# M3_Chip.net
KiCad netlist of a schematic drawn in Altium Designer
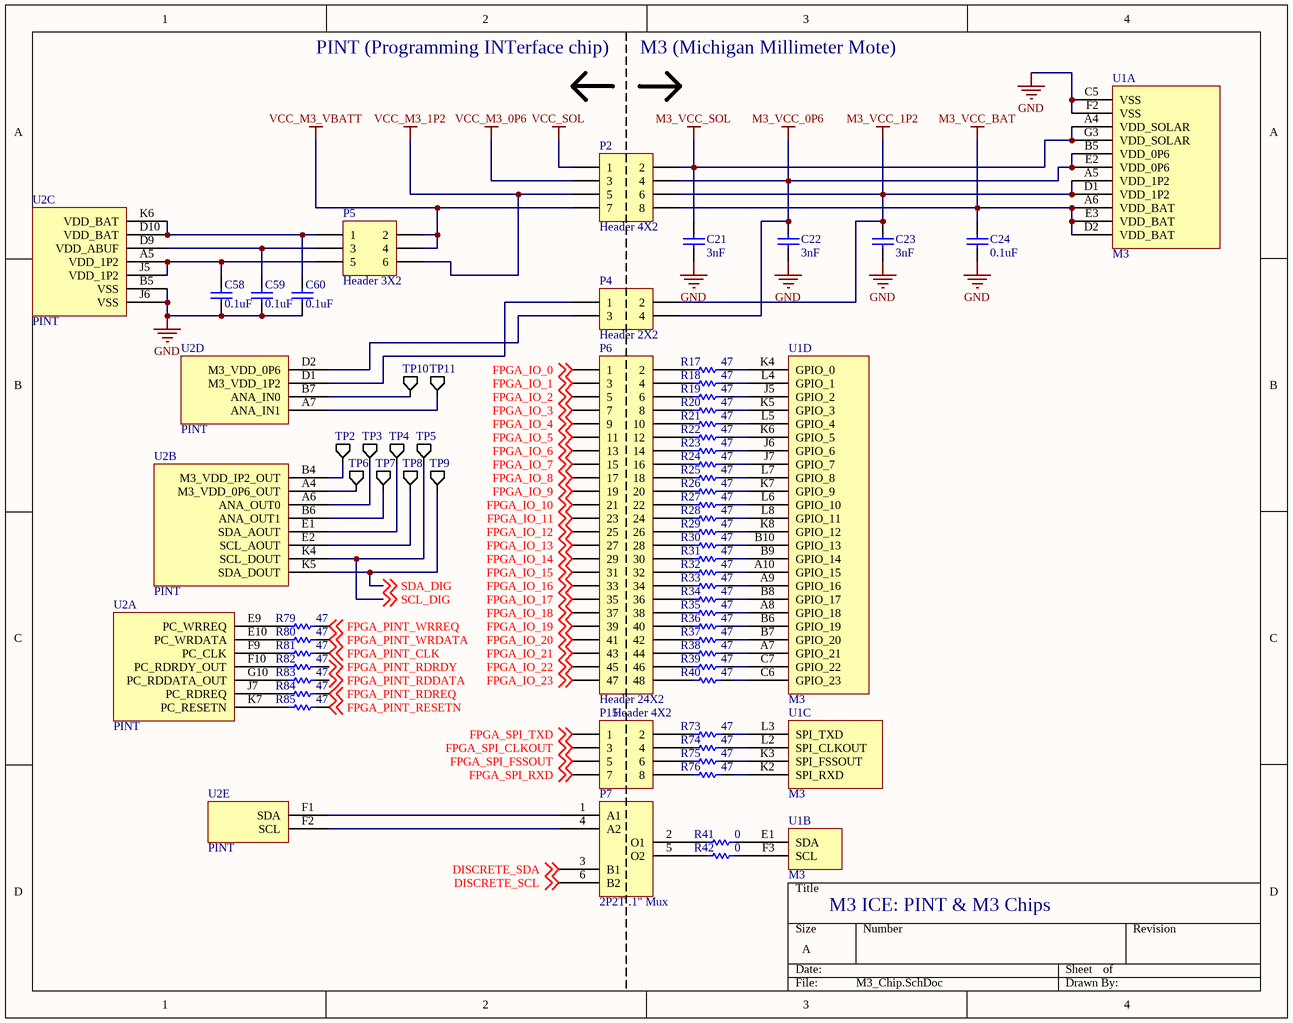
[diagram p0: M3_Chip.SchDoc]

(export (version "E")
  (design (tool "Eeschema 10.0.6"))
  (components
    (comp (ref "C21")
      (value "3nF")
      (footprint "1608[0603]")
      (description "Capacitor (Semiconductor SIM Model)")
      (fields
        (field (name "DISTPARTNO") "399-7893-1-ND")
        (field (name "MANPARTNO") "C0603C302K5GACTU")
        (field (name "PUBLISHER") "Altium Limited")
      )
      (libsource (lib "Miscellaneous Devices") (part "Cap Semi"))
    )
    (comp (ref "C22")
      (value "3nF")
      (footprint "1608[0603]")
      (description "Capacitor (Semiconductor SIM Model)")
      (fields
        (field (name "DISTPARTNO") "399-7893-1-ND")
        (field (name "MANPARTNO") "C0603C302K5GACTU")
        (field (name "PUBLISHER") "Altium Limited")
      )
      (libsource (lib "Miscellaneous Devices") (part "Cap Semi"))
    )
    (comp (ref "C23")
      (value "3nF")
      (footprint "1608[0603]")
      (description "Capacitor (Semiconductor SIM Model)")
      (fields
        (field (name "DISTPARTNO") "399-7893-1-ND")
        (field (name "MANPARTNO") "C0603C302K5GACTU")
        (field (name "PUBLISHER") "Altium Limited")
      )
      (libsource (lib "Miscellaneous Devices") (part "Cap Semi"))
    )
    (comp (ref "C24")
      (value "0.1uF")
      (footprint "1608[0603]")
      (description "Capacitor (Semiconductor SIM Model)")
      (fields
        (field (name "DISTPARTNO") "445-1317-1-ND")
        (field (name "MANPARTNO") "C1608X7R1C104K")
        (field (name "PUBLISHER") "Altium Limited")
      )
      (libsource (lib "Miscellaneous Devices") (part "Cap Semi"))
    )
    (comp (ref "C58")
      (value "0.1uF")
      (footprint "1608[0603]")
      (description "Capacitor (Semiconductor SIM Model)")
      (fields
        (field (name "DISTPARTNO") "445-1317-1-ND")
        (field (name "MANPARTNO") "C1608X7R1C104K")
        (field (name "PUBLISHER") "Altium Limited")
      )
      (libsource (lib "Miscellaneous Devices") (part "Cap Semi"))
    )
    (comp (ref "C59")
      (value "0.1uF")
      (footprint "1608[0603]")
      (description "Capacitor (Semiconductor SIM Model)")
      (fields
        (field (name "DISTPARTNO") "445-1317-1-ND")
        (field (name "MANPARTNO") "C1608X7R1C104K")
        (field (name "PUBLISHER") "Altium Limited")
      )
      (libsource (lib "Miscellaneous Devices") (part "Cap Semi"))
    )
    (comp (ref "C60")
      (value "0.1uF")
      (footprint "1608[0603]")
      (description "Capacitor (Semiconductor SIM Model)")
      (fields
        (field (name "DISTPARTNO") "445-1317-1-ND")
        (field (name "MANPARTNO") "C1608X7R1C104K")
        (field (name "PUBLISHER") "Altium Limited")
      )
      (libsource (lib "Miscellaneous Devices") (part "Cap Semi"))
    )
    (comp (ref "P2")
      (value "Header 4X2")
      (footprint "HDR2X4")
      (description "Header, 4-Pin, Dual row")
      (fields (field (name "PUBLISHER") "Altium Limited"))
      (libsource (lib "Miscellaneous Connectors") (part "Header 4X2"))
    )
    (comp (ref "P4")
      (value "Header 2X2")
      (footprint "HDR2X2")
      (description "Header, 2-Pin, Dual row")
      (fields (field (name "PUBLISHER") "Altium Limited"))
      (libsource (lib "Miscellaneous Connectors") (part "Header 2X2"))
    )
    (comp (ref "P5")
      (value "Header 3X2")
      (footprint "HDR2X3")
      (description "Header, 3-Pin, Dual row")
      (fields (field (name "PUBLISHER") "Altium Limited"))
      (libsource (lib "Miscellaneous Connectors") (part "Header 3X2"))
    )
    (comp (ref "P6")
      (value "Header 24X2")
      (footprint "HDR2X24")
      (description "Header, 24-Pin, Dual row")
      (fields (field (name "MANPARTNO") "4-103328-0") (field (name "PUBLISHER") "Altium Limited"))
      (libsource (lib "Miscellaneous Connectors") (part "Header 24X2"))
    )
    (comp (ref "P7")
      (value "2P2T .1\" Mux")
      (footprint "HDR3x2")
      (libsource (lib "M3") (part "2P2T .1{dblquote} Mux"))
    )
    (comp (ref "P15")
      (value "Header 4X2")
      (footprint "HDR2X4")
      (description "Header, 4-Pin, Dual row")
      (fields (field (name "PUBLISHER") "Altium Limited"))
      (libsource (lib "Miscellaneous Connectors") (part "Header 4X2"))
    )
    (comp (ref "R17")
      (value "47")
      (footprint "0603")
      (description "Semiconductor Resistor")
      (fields
        (field (name "DISTPARTNO") "P47GCT-ND")
        (field (name "MANPARTNO") "ERJ-3GEYJ470V")
        (field (name "PUBLISHER") "Altium Limited")
      )
      (libsource (lib "M3") (part "Res Chip"))
    )
    (comp (ref "R18")
      (value "47")
      (footprint "0603")
      (description "Semiconductor Resistor")
      (fields
        (field (name "DISTPARTNO") "P47GCT-ND")
        (field (name "MANPARTNO") "ERJ-3GEYJ470V")
        (field (name "PUBLISHER") "Altium Limited")
      )
      (libsource (lib "M3") (part "Res Chip"))
    )
    (comp (ref "R19")
      (value "47")
      (footprint "0603")
      (description "Semiconductor Resistor")
      (fields
        (field (name "DISTPARTNO") "P47GCT-ND")
        (field (name "MANPARTNO") "ERJ-3GEYJ470V")
        (field (name "PUBLISHER") "Altium Limited")
      )
      (libsource (lib "M3") (part "Res Chip"))
    )
    (comp (ref "R20")
      (value "47")
      (footprint "0603")
      (description "Semiconductor Resistor")
      (fields
        (field (name "DISTPARTNO") "P47GCT-ND")
        (field (name "MANPARTNO") "ERJ-3GEYJ470V")
        (field (name "PUBLISHER") "Altium Limited")
      )
      (libsource (lib "M3") (part "Res Chip"))
    )
    (comp (ref "R21")
      (value "47")
      (footprint "0603")
      (description "Semiconductor Resistor")
      (fields
        (field (name "DISTPARTNO") "P47GCT-ND")
        (field (name "MANPARTNO") "ERJ-3GEYJ470V")
        (field (name "PUBLISHER") "Altium Limited")
      )
      (libsource (lib "M3") (part "Res Chip"))
    )
    (comp (ref "R22")
      (value "47")
      (footprint "0603")
      (description "Semiconductor Resistor")
      (fields
        (field (name "DISTPARTNO") "P47GCT-ND")
        (field (name "MANPARTNO") "ERJ-3GEYJ470V")
        (field (name "PUBLISHER") "Altium Limited")
      )
      (libsource (lib "M3") (part "Res Chip"))
    )
    (comp (ref "R23")
      (value "47")
      (footprint "0603")
      (description "Semiconductor Resistor")
      (fields
        (field (name "DISTPARTNO") "P47GCT-ND")
        (field (name "MANPARTNO") "ERJ-3GEYJ470V")
        (field (name "PUBLISHER") "Altium Limited")
      )
      (libsource (lib "M3") (part "Res Chip"))
    )
    (comp (ref "R24")
      (value "47")
      (footprint "0603")
      (description "Semiconductor Resistor")
      (fields
        (field (name "DISTPARTNO") "P47GCT-ND")
        (field (name "MANPARTNO") "ERJ-3GEYJ470V")
        (field (name "PUBLISHER") "Altium Limited")
      )
      (libsource (lib "M3") (part "Res Chip"))
    )
    (comp (ref "R25")
      (value "47")
      (footprint "0603")
      (description "Semiconductor Resistor")
      (fields
        (field (name "DISTPARTNO") "P47GCT-ND")
        (field (name "MANPARTNO") "ERJ-3GEYJ470V")
        (field (name "PUBLISHER") "Altium Limited")
      )
      (libsource (lib "M3") (part "Res Chip"))
    )
    (comp (ref "R26")
      (value "47")
      (footprint "0603")
      (description "Semiconductor Resistor")
      (fields
        (field (name "DISTPARTNO") "P47GCT-ND")
        (field (name "MANPARTNO") "ERJ-3GEYJ470V")
        (field (name "PUBLISHER") "Altium Limited")
      )
      (libsource (lib "M3") (part "Res Chip"))
    )
    (comp (ref "R27")
      (value "47")
      (footprint "0603")
      (description "Semiconductor Resistor")
      (fields
        (field (name "DISTPARTNO") "P47GCT-ND")
        (field (name "MANPARTNO") "ERJ-3GEYJ470V")
        (field (name "PUBLISHER") "Altium Limited")
      )
      (libsource (lib "M3") (part "Res Chip"))
    )
    (comp (ref "R28")
      (value "47")
      (footprint "0603")
      (description "Semiconductor Resistor")
      (fields
        (field (name "DISTPARTNO") "P47GCT-ND")
        (field (name "MANPARTNO") "ERJ-3GEYJ470V")
        (field (name "PUBLISHER") "Altium Limited")
      )
      (libsource (lib "M3") (part "Res Chip"))
    )
    (comp (ref "R29")
      (value "47")
      (footprint "0603")
      (description "Semiconductor Resistor")
      (fields
        (field (name "DISTPARTNO") "P47GCT-ND")
        (field (name "MANPARTNO") "ERJ-3GEYJ470V")
        (field (name "PUBLISHER") "Altium Limited")
      )
      (libsource (lib "M3") (part "Res Chip"))
    )
    (comp (ref "R30")
      (value "47")
      (footprint "0603")
      (description "Semiconductor Resistor")
      (fields
        (field (name "DISTPARTNO") "P47GCT-ND")
        (field (name "MANPARTNO") "ERJ-3GEYJ470V")
        (field (name "PUBLISHER") "Altium Limited")
      )
      (libsource (lib "M3") (part "Res Chip"))
    )
    (comp (ref "R31")
      (value "47")
      (footprint "0603")
      (description "Semiconductor Resistor")
      (fields
        (field (name "DISTPARTNO") "P47GCT-ND")
        (field (name "MANPARTNO") "ERJ-3GEYJ470V")
        (field (name "PUBLISHER") "Altium Limited")
      )
      (libsource (lib "M3") (part "Res Chip"))
    )
    (comp (ref "R32")
      (value "47")
      (footprint "0603")
      (description "Semiconductor Resistor")
      (fields
        (field (name "DISTPARTNO") "P47GCT-ND")
        (field (name "MANPARTNO") "ERJ-3GEYJ470V")
        (field (name "PUBLISHER") "Altium Limited")
      )
      (libsource (lib "M3") (part "Res Chip"))
    )
    (comp (ref "R33")
      (value "47")
      (footprint "0603")
      (description "Semiconductor Resistor")
      (fields
        (field (name "DISTPARTNO") "P47GCT-ND")
        (field (name "MANPARTNO") "ERJ-3GEYJ470V")
        (field (name "PUBLISHER") "Altium Limited")
      )
      (libsource (lib "M3") (part "Res Chip"))
    )
    (comp (ref "R34")
      (value "47")
      (footprint "0603")
      (description "Semiconductor Resistor")
      (fields
        (field (name "DISTPARTNO") "P47GCT-ND")
        (field (name "MANPARTNO") "ERJ-3GEYJ470V")
        (field (name "PUBLISHER") "Altium Limited")
      )
      (libsource (lib "M3") (part "Res Chip"))
    )
    (comp (ref "R35")
      (value "47")
      (footprint "0603")
      (description "Semiconductor Resistor")
      (fields
        (field (name "DISTPARTNO") "P47GCT-ND")
        (field (name "MANPARTNO") "ERJ-3GEYJ470V")
        (field (name "PUBLISHER") "Altium Limited")
      )
      (libsource (lib "M3") (part "Res Chip"))
    )
    (comp (ref "R36")
      (value "47")
      (footprint "0603")
      (description "Semiconductor Resistor")
      (fields
        (field (name "DISTPARTNO") "P47GCT-ND")
        (field (name "MANPARTNO") "ERJ-3GEYJ470V")
        (field (name "PUBLISHER") "Altium Limited")
      )
      (libsource (lib "M3") (part "Res Chip"))
    )
    (comp (ref "R37")
      (value "47")
      (footprint "0603")
      (description "Semiconductor Resistor")
      (fields
        (field (name "DISTPARTNO") "P47GCT-ND")
        (field (name "MANPARTNO") "ERJ-3GEYJ470V")
        (field (name "PUBLISHER") "Altium Limited")
      )
      (libsource (lib "M3") (part "Res Chip"))
    )
    (comp (ref "R38")
      (value "47")
      (footprint "0603")
      (description "Semiconductor Resistor")
      (fields
        (field (name "DISTPARTNO") "P47GCT-ND")
        (field (name "MANPARTNO") "ERJ-3GEYJ470V")
        (field (name "PUBLISHER") "Altium Limited")
      )
      (libsource (lib "M3") (part "Res Chip"))
    )
    (comp (ref "R39")
      (value "47")
      (footprint "0603")
      (description "Semiconductor Resistor")
      (fields
        (field (name "DISTPARTNO") "P47GCT-ND")
        (field (name "MANPARTNO") "ERJ-3GEYJ470V")
        (field (name "PUBLISHER") "Altium Limited")
      )
      (libsource (lib "M3") (part "Res Chip"))
    )
    (comp (ref "R40")
      (value "47")
      (footprint "0603")
      (description "Semiconductor Resistor")
      (fields
        (field (name "DISTPARTNO") "P47GCT-ND")
        (field (name "MANPARTNO") "ERJ-3GEYJ470V")
        (field (name "PUBLISHER") "Altium Limited")
      )
      (libsource (lib "M3") (part "Res Chip"))
    )
    (comp (ref "R41")
      (value "0")
      (footprint "0603")
      (description "Semiconductor Resistor")
      (fields
        (field (name "DISTPARTNO") "P0.0GCT-ND")
        (field (name "MANPARTNO") "ERJ-3GEY0R00V")
        (field (name "PUBLISHER") "Altium Limited")
      )
      (libsource (lib "M3") (part "Res Chip"))
    )
    (comp (ref "R42")
      (value "0")
      (footprint "0603")
      (description "Semiconductor Resistor")
      (fields
        (field (name "DISTPARTNO") "P0.0GCT-ND")
        (field (name "MANPARTNO") "ERJ-3GEY0R00V")
        (field (name "PUBLISHER") "Altium Limited")
      )
      (libsource (lib "M3") (part "Res Chip"))
    )
    (comp (ref "R73")
      (value "47")
      (footprint "0603")
      (description "Semiconductor Resistor")
      (fields
        (field (name "DISTPARTNO") "P47GCT-ND")
        (field (name "MANPARTNO") "ERJ-3GEYJ470V")
        (field (name "PUBLISHER") "Altium Limited")
      )
      (libsource (lib "M3") (part "Res Chip"))
    )
    (comp (ref "R74")
      (value "47")
      (footprint "0603")
      (description "Semiconductor Resistor")
      (fields
        (field (name "DISTPARTNO") "P47GCT-ND")
        (field (name "MANPARTNO") "ERJ-3GEYJ470V")
        (field (name "PUBLISHER") "Altium Limited")
      )
      (libsource (lib "M3") (part "Res Chip"))
    )
    (comp (ref "R75")
      (value "47")
      (footprint "0603")
      (description "Semiconductor Resistor")
      (fields
        (field (name "DISTPARTNO") "P47GCT-ND")
        (field (name "MANPARTNO") "ERJ-3GEYJ470V")
        (field (name "PUBLISHER") "Altium Limited")
      )
      (libsource (lib "M3") (part "Res Chip"))
    )
    (comp (ref "R76")
      (value "47")
      (footprint "0603")
      (description "Semiconductor Resistor")
      (fields
        (field (name "DISTPARTNO") "P47GCT-ND")
        (field (name "MANPARTNO") "ERJ-3GEYJ470V")
        (field (name "PUBLISHER") "Altium Limited")
      )
      (libsource (lib "M3") (part "Res Chip"))
    )
    (comp (ref "R79")
      (value "47")
      (footprint "0603")
      (description "Semiconductor Resistor")
      (fields
        (field (name "DISTPARTNO") "P47GCT-ND")
        (field (name "MANPARTNO") "ERJ-3GEYJ470V")
        (field (name "PUBLISHER") "Altium Limited")
      )
      (libsource (lib "M3") (part "Res Chip"))
    )
    (comp (ref "R80")
      (value "47")
      (footprint "0603")
      (description "Semiconductor Resistor")
      (fields
        (field (name "DISTPARTNO") "P47GCT-ND")
        (field (name "MANPARTNO") "ERJ-3GEYJ470V")
        (field (name "PUBLISHER") "Altium Limited")
      )
      (libsource (lib "M3") (part "Res Chip"))
    )
    (comp (ref "R81")
      (value "47")
      (footprint "0603")
      (description "Semiconductor Resistor")
      (fields
        (field (name "DISTPARTNO") "P47GCT-ND")
        (field (name "MANPARTNO") "ERJ-3GEYJ470V")
        (field (name "PUBLISHER") "Altium Limited")
      )
      (libsource (lib "M3") (part "Res Chip"))
    )
    (comp (ref "R82")
      (value "47")
      (footprint "0603")
      (description "Semiconductor Resistor")
      (fields
        (field (name "DISTPARTNO") "P47GCT-ND")
        (field (name "MANPARTNO") "ERJ-3GEYJ470V")
        (field (name "PUBLISHER") "Altium Limited")
      )
      (libsource (lib "M3") (part "Res Chip"))
    )
    (comp (ref "R83")
      (value "47")
      (footprint "0603")
      (description "Semiconductor Resistor")
      (fields
        (field (name "DISTPARTNO") "P47GCT-ND")
        (field (name "MANPARTNO") "ERJ-3GEYJ470V")
        (field (name "PUBLISHER") "Altium Limited")
      )
      (libsource (lib "M3") (part "Res Chip"))
    )
    (comp (ref "R84")
      (value "47")
      (footprint "0603")
      (description "Semiconductor Resistor")
      (fields
        (field (name "DISTPARTNO") "P47GCT-ND")
        (field (name "MANPARTNO") "ERJ-3GEYJ470V")
        (field (name "PUBLISHER") "Altium Limited")
      )
      (libsource (lib "M3") (part "Res Chip"))
    )
    (comp (ref "R85")
      (value "47")
      (footprint "0603")
      (description "Semiconductor Resistor")
      (fields
        (field (name "DISTPARTNO") "P47GCT-ND")
        (field (name "MANPARTNO") "ERJ-3GEYJ470V")
        (field (name "PUBLISHER") "Altium Limited")
      )
      (libsource (lib "M3") (part "Res Chip"))
    )
    (comp (ref "TP2") (value "TP") (footprint "TP") (libsource (lib "M3") (part "TP")))
    (comp (ref "TP3") (value "TP") (footprint "TP") (libsource (lib "M3") (part "TP")))
    (comp (ref "TP4") (value "TP") (footprint "TP") (libsource (lib "M3") (part "TP")))
    (comp (ref "TP5") (value "TP") (footprint "TP") (libsource (lib "M3") (part "TP")))
    (comp (ref "TP6") (value "TP") (footprint "TP") (libsource (lib "M3") (part "TP")))
    (comp (ref "TP7") (value "TP") (footprint "TP") (libsource (lib "M3") (part "TP")))
    (comp (ref "TP8") (value "TP") (footprint "TP") (libsource (lib "M3") (part "TP")))
    (comp (ref "TP9") (value "TP") (footprint "TP") (libsource (lib "M3") (part "TP")))
    (comp (ref "TP10") (value "TP") (footprint "TP") (libsource (lib "M3") (part "TP")))
    (comp (ref "TP11") (value "TP") (footprint "TP") (libsource (lib "M3") (part "TP")))
    (comp (ref "U1")
      (value "M3")
      (footprint "CPGA-84")
      (fields (field (name "DISTPARTNO") "3M5067-ND") (field (name "MANPARTNO") "200-6311-9UN-1900"))
      (libsource (lib "") (part "M3_1"))
    )
    (comp (ref "U2")
      (value "PINT")
      (footprint "CPGA-65")
      (fields (field (name "DISTPARTNO") "3M5066-ND") (field (name "MANPARTNO") "200-6310-9UN-1900"))
      (libsource (lib "M3") (part "PINT"))
    )
  )
  (nets
    (net (code "1") (name "DISCRETE_SCL") (class "Default")
      (node (ref "P7") (pin "6") (pinfunction "B2_6") (pintype "passive"))
    )
    (net (code "2") (name "DISCRETE_SDA") (class "Default")
      (node (ref "P7") (pin "3") (pinfunction "B1_3") (pintype "passive"))
    )
    (net (code "3") (name "FPGA_IO_0") (class "Default")
      (node (ref "P6") (pin "1") (pinfunction "1_1") (pintype "passive"))
    )
    (net (code "4") (name "FPGA_IO_1") (class "Default")
      (node (ref "P6") (pin "3") (pinfunction "3_3") (pintype "passive"))
    )
    (net (code "5") (name "FPGA_IO_2") (class "Default")
      (node (ref "P6") (pin "5") (pinfunction "5_5") (pintype "passive"))
    )
    (net (code "6") (name "FPGA_IO_3") (class "Default")
      (node (ref "P6") (pin "7") (pinfunction "7_7") (pintype "passive"))
    )
    (net (code "7") (name "FPGA_IO_4") (class "Default")
      (node (ref "P6") (pin "9") (pinfunction "9_9") (pintype "passive"))
    )
    (net (code "8") (name "FPGA_IO_5") (class "Default")
      (node (ref "P6") (pin "11") (pinfunction "11_11") (pintype "passive"))
    )
    (net (code "9") (name "FPGA_IO_6") (class "Default")
      (node (ref "P6") (pin "13") (pinfunction "13_13") (pintype "passive"))
    )
    (net (code "10") (name "FPGA_IO_7") (class "Default")
      (node (ref "P6") (pin "15") (pinfunction "15_15") (pintype "passive"))
    )
    (net (code "11") (name "FPGA_IO_8") (class "Default")
      (node (ref "P6") (pin "17") (pinfunction "17_17") (pintype "passive"))
    )
    (net (code "12") (name "FPGA_IO_9") (class "Default")
      (node (ref "P6") (pin "19") (pinfunction "19_19") (pintype "passive"))
    )
    (net (code "13") (name "FPGA_IO_10") (class "Default")
      (node (ref "P6") (pin "21") (pinfunction "21_21") (pintype "passive"))
    )
    (net (code "14") (name "FPGA_IO_11") (class "Default")
      (node (ref "P6") (pin "23") (pinfunction "23_23") (pintype "passive"))
    )
    (net (code "15") (name "FPGA_IO_12") (class "Default")
      (node (ref "P6") (pin "25") (pinfunction "25_25") (pintype "passive"))
    )
    (net (code "16") (name "FPGA_IO_13") (class "Default")
      (node (ref "P6") (pin "27") (pinfunction "27_27") (pintype "passive"))
    )
    (net (code "17") (name "FPGA_IO_14") (class "Default")
      (node (ref "P6") (pin "29") (pinfunction "29_29") (pintype "passive"))
    )
    (net (code "18") (name "FPGA_IO_15") (class "Default")
      (node (ref "P6") (pin "31") (pinfunction "31_31") (pintype "passive"))
    )
    (net (code "19") (name "FPGA_IO_16") (class "Default")
      (node (ref "P6") (pin "33") (pinfunction "33_33") (pintype "passive"))
    )
    (net (code "20") (name "FPGA_IO_17") (class "Default")
      (node (ref "P6") (pin "35") (pinfunction "35_35") (pintype "passive"))
    )
    (net (code "21") (name "FPGA_IO_18") (class "Default")
      (node (ref "P6") (pin "37") (pinfunction "37_37") (pintype "passive"))
    )
    (net (code "22") (name "FPGA_IO_19") (class "Default")
      (node (ref "P6") (pin "39") (pinfunction "39_39") (pintype "passive"))
    )
    (net (code "23") (name "FPGA_IO_20") (class "Default")
      (node (ref "P6") (pin "41") (pinfunction "41_41") (pintype "passive"))
    )
    (net (code "24") (name "FPGA_IO_21") (class "Default")
      (node (ref "P6") (pin "43") (pinfunction "43_43") (pintype "passive"))
    )
    (net (code "25") (name "FPGA_IO_22") (class "Default")
      (node (ref "P6") (pin "45") (pinfunction "45_45") (pintype "passive"))
    )
    (net (code "26") (name "FPGA_IO_23") (class "Default")
      (node (ref "P6") (pin "47") (pinfunction "47_47") (pintype "passive"))
    )
    (net (code "27") (name "FPGA_PINT_CLK") (class "Default")
      (node (ref "R81") (pin "1") (pinfunction "1_1") (pintype "passive"))
    )
    (net (code "28") (name "FPGA_PINT_RDDATA") (class "Default")
      (node (ref "R83") (pin "1") (pinfunction "1_1") (pintype "passive"))
    )
    (net (code "29") (name "FPGA_PINT_RDRDY") (class "Default")
      (node (ref "R82") (pin "1") (pinfunction "1_1") (pintype "passive"))
    )
    (net (code "30") (name "FPGA_PINT_RDREQ") (class "Default")
      (node (ref "R84") (pin "1") (pinfunction "1_1") (pintype "passive"))
    )
    (net (code "31") (name "FPGA_PINT_RESETN") (class "Default")
      (node (ref "R85") (pin "1") (pinfunction "1_1") (pintype "passive"))
    )
    (net (code "32") (name "FPGA_PINT_WRDATA") (class "Default")
      (node (ref "R80") (pin "1") (pinfunction "1_1") (pintype "passive"))
    )
    (net (code "33") (name "FPGA_PINT_WRREQ") (class "Default")
      (node (ref "R79") (pin "1") (pinfunction "1_1") (pintype "passive"))
    )
    (net (code "34") (name "FPGA_SPI_CLKOUT") (class "Default")
      (node (ref "P15") (pin "3") (pinfunction "3_3") (pintype "passive"))
    )
    (net (code "35") (name "FPGA_SPI_FSSOUT") (class "Default")
      (node (ref "P15") (pin "5") (pinfunction "5_5") (pintype "passive"))
    )
    (net (code "36") (name "FPGA_SPI_RXD") (class "Default")
      (node (ref "P15") (pin "7") (pinfunction "7_7") (pintype "passive"))
    )
    (net (code "37") (name "FPGA_SPI_TXD") (class "Default")
      (node (ref "P15") (pin "1") (pinfunction "1_1") (pintype "passive"))
    )
    (net (code "38") (name "GND") (class "Default")
      (node (ref "C21") (pin "1") (pinfunction "1_1") (pintype "passive"))
      (node (ref "C22") (pin "1") (pinfunction "1_1") (pintype "passive"))
      (node (ref "C23") (pin "1") (pinfunction "1_1") (pintype "passive"))
      (node (ref "C24") (pin "1") (pinfunction "1_1") (pintype "passive"))
      (node (ref "C58") (pin "1") (pinfunction "1_1") (pintype "passive"))
      (node (ref "C59") (pin "1") (pinfunction "1_1") (pintype "passive"))
      (node (ref "C60") (pin "1") (pinfunction "1_1") (pintype "passive"))
      (node (ref "U1") (pin "C5") (pinfunction "VSS_C5") (pintype "passive"))
      (node (ref "U1") (pin "F2") (pinfunction "VSS_F2") (pintype "passive"))
      (node (ref "U2") (pin "B5") (pinfunction "VSS_B5") (pintype "passive"))
      (node (ref "U2") (pin "J6") (pinfunction "VSS_J6") (pintype "passive"))
    )
    (net (code "39") (name "M3_VCC_0P6") (class "Default")
      (node (ref "C22") (pin "2") (pinfunction "2_2") (pintype "passive"))
      (node (ref "P2") (pin "4") (pinfunction "4_4") (pintype "passive"))
      (node (ref "P4") (pin "4") (pinfunction "4_4") (pintype "passive"))
      (node (ref "U1") (pin "B5") (pinfunction "VDD_0P6_B5") (pintype "passive"))
      (node (ref "U1") (pin "E2") (pinfunction "VDD_0P6_E2") (pintype "passive"))
    )
    (net (code "40") (name "M3_VCC_1P2") (class "Default")
      (node (ref "C23") (pin "2") (pinfunction "2_2") (pintype "passive"))
      (node (ref "P2") (pin "6") (pinfunction "6_6") (pintype "passive"))
      (node (ref "P4") (pin "2") (pinfunction "2_2") (pintype "passive"))
      (node (ref "U1") (pin "A5") (pinfunction "VDD_1P2_A5") (pintype "passive"))
      (node (ref "U1") (pin "D1") (pinfunction "VDD_1P2_D1") (pintype "passive"))
    )
    (net (code "41") (name "M3_VCC_BAT") (class "Default")
      (node (ref "C24") (pin "2") (pinfunction "2_2") (pintype "passive"))
      (node (ref "P2") (pin "8") (pinfunction "8_8") (pintype "passive"))
      (node (ref "U1") (pin "A6") (pinfunction "VDD_BAT_A6") (pintype "passive"))
      (node (ref "U1") (pin "D2") (pinfunction "VDD_BAT_D2") (pintype "passive"))
      (node (ref "U1") (pin "E3") (pinfunction "VDD_BAT_E3") (pintype "passive"))
    )
    (net (code "42") (name "M3_VCC_SOL") (class "Default")
      (node (ref "C21") (pin "2") (pinfunction "2_2") (pintype "passive"))
      (node (ref "P2") (pin "2") (pinfunction "2_2") (pintype "passive"))
      (node (ref "U1") (pin "A4") (pinfunction "VDD_SOLAR_A4") (pintype "passive"))
      (node (ref "U1") (pin "G3") (pinfunction "VDD_SOLAR_G3") (pintype "passive"))
    )
    (net (code "43") (name "Net-(C58-Pad2)") (class "Default")
      (node (ref "C58") (pin "2") (pinfunction "2_2") (pintype "passive"))
      (node (ref "P5") (pin "5") (pinfunction "5_5") (pintype "passive"))
      (node (ref "U2") (pin "A5") (pinfunction "VDD_1P2_A5") (pintype "passive"))
      (node (ref "U2") (pin "J5") (pinfunction "VDD_1P2_J5") (pintype "passive"))
    )
    (net (code "44") (name "Net-(C60-Pad2)") (class "Default")
      (node (ref "C60") (pin "2") (pinfunction "2_2") (pintype "passive"))
      (node (ref "P5") (pin "1") (pinfunction "1_1") (pintype "passive"))
      (node (ref "U2") (pin "D10") (pinfunction "VDD_BAT_D10") (pintype "passive"))
      (node (ref "U2") (pin "K6") (pinfunction "VDD_BAT_K6") (pintype "passive"))
    )
    (net (code "45") (name "Net-(P6-Pad2)") (class "Default")
      (node (ref "P6") (pin "2") (pinfunction "2_2") (pintype "passive"))
      (node (ref "R17") (pin "2") (pinfunction "2_2") (pintype "passive"))
    )
    (net (code "46") (name "Net-(P6-Pad4)") (class "Default")
      (node (ref "P6") (pin "4") (pinfunction "4_4") (pintype "passive"))
      (node (ref "R18") (pin "2") (pinfunction "2_2") (pintype "passive"))
    )
    (net (code "47") (name "Net-(P6-Pad6)") (class "Default")
      (node (ref "P6") (pin "6") (pinfunction "6_6") (pintype "passive"))
      (node (ref "R19") (pin "2") (pinfunction "2_2") (pintype "passive"))
    )
    (net (code "48") (name "Net-(P6-Pad8)") (class "Default")
      (node (ref "P6") (pin "8") (pinfunction "8_8") (pintype "passive"))
      (node (ref "R20") (pin "2") (pinfunction "2_2") (pintype "passive"))
    )
    (net (code "49") (name "Net-(P6-Pad10)") (class "Default")
      (node (ref "P6") (pin "10") (pinfunction "10_10") (pintype "passive"))
      (node (ref "R21") (pin "2") (pinfunction "2_2") (pintype "passive"))
    )
    (net (code "50") (name "Net-(P6-Pad12)") (class "Default")
      (node (ref "P6") (pin "12") (pinfunction "12_12") (pintype "passive"))
      (node (ref "R22") (pin "2") (pinfunction "2_2") (pintype "passive"))
    )
    (net (code "51") (name "Net-(P6-Pad14)") (class "Default")
      (node (ref "P6") (pin "14") (pinfunction "14_14") (pintype "passive"))
      (node (ref "R23") (pin "2") (pinfunction "2_2") (pintype "passive"))
    )
    (net (code "52") (name "Net-(P6-Pad16)") (class "Default")
      (node (ref "P6") (pin "16") (pinfunction "16_16") (pintype "passive"))
      (node (ref "R24") (pin "2") (pinfunction "2_2") (pintype "passive"))
    )
    (net (code "53") (name "Net-(P6-Pad18)") (class "Default")
      (node (ref "P6") (pin "18") (pinfunction "18_18") (pintype "passive"))
      (node (ref "R25") (pin "2") (pinfunction "2_2") (pintype "passive"))
    )
    (net (code "54") (name "Net-(P6-Pad20)") (class "Default")
      (node (ref "P6") (pin "20") (pinfunction "20_20") (pintype "passive"))
      (node (ref "R26") (pin "2") (pinfunction "2_2") (pintype "passive"))
    )
    (net (code "55") (name "Net-(P6-Pad22)") (class "Default")
      (node (ref "P6") (pin "22") (pinfunction "22_22") (pintype "passive"))
      (node (ref "R27") (pin "2") (pinfunction "2_2") (pintype "passive"))
    )
    (net (code "56") (name "Net-(P6-Pad24)") (class "Default")
      (node (ref "P6") (pin "24") (pinfunction "24_24") (pintype "passive"))
      (node (ref "R28") (pin "2") (pinfunction "2_2") (pintype "passive"))
    )
    (net (code "57") (name "Net-(P6-Pad26)") (class "Default")
      (node (ref "P6") (pin "26") (pinfunction "26_26") (pintype "passive"))
      (node (ref "R29") (pin "2") (pinfunction "2_2") (pintype "passive"))
    )
    (net (code "58") (name "Net-(P6-Pad28)") (class "Default")
      (node (ref "P6") (pin "28") (pinfunction "28_28") (pintype "passive"))
      (node (ref "R30") (pin "2") (pinfunction "2_2") (pintype "passive"))
    )
    (net (code "59") (name "Net-(P6-Pad30)") (class "Default")
      (node (ref "P6") (pin "30") (pinfunction "30_30") (pintype "passive"))
      (node (ref "R31") (pin "2") (pinfunction "2_2") (pintype "passive"))
    )
    (net (code "60") (name "Net-(P6-Pad32)") (class "Default")
      (node (ref "P6") (pin "32") (pinfunction "32_32") (pintype "passive"))
      (node (ref "R32") (pin "2") (pinfunction "2_2") (pintype "passive"))
    )
    (net (code "61") (name "Net-(P6-Pad34)") (class "Default")
      (node (ref "P6") (pin "34") (pinfunction "34_34") (pintype "passive"))
      (node (ref "R33") (pin "2") (pinfunction "2_2") (pintype "passive"))
    )
    (net (code "62") (name "Net-(P6-Pad36)") (class "Default")
      (node (ref "P6") (pin "36") (pinfunction "36_36") (pintype "passive"))
      (node (ref "R34") (pin "2") (pinfunction "2_2") (pintype "passive"))
    )
    (net (code "63") (name "Net-(P6-Pad38)") (class "Default")
      (node (ref "P6") (pin "38") (pinfunction "38_38") (pintype "passive"))
      (node (ref "R35") (pin "2") (pinfunction "2_2") (pintype "passive"))
    )
    (net (code "64") (name "Net-(P6-Pad40)") (class "Default")
      (node (ref "P6") (pin "40") (pinfunction "40_40") (pintype "passive"))
      (node (ref "R36") (pin "2") (pinfunction "2_2") (pintype "passive"))
    )
    (net (code "65") (name "Net-(P6-Pad42)") (class "Default")
      (node (ref "P6") (pin "42") (pinfunction "42_42") (pintype "passive"))
      (node (ref "R37") (pin "2") (pinfunction "2_2") (pintype "passive"))
    )
    (net (code "66") (name "Net-(P6-Pad44)") (class "Default")
      (node (ref "P6") (pin "44") (pinfunction "44_44") (pintype "passive"))
      (node (ref "R38") (pin "2") (pinfunction "2_2") (pintype "passive"))
    )
    (net (code "67") (name "Net-(P6-Pad46)") (class "Default")
      (node (ref "P6") (pin "46") (pinfunction "46_46") (pintype "passive"))
      (node (ref "R39") (pin "2") (pinfunction "2_2") (pintype "passive"))
    )
    (net (code "68") (name "Net-(P6-Pad48)") (class "Default")
      (node (ref "P6") (pin "48") (pinfunction "48_48") (pintype "passive"))
      (node (ref "R40") (pin "2") (pinfunction "2_2") (pintype "passive"))
    )
    (net (code "69") (name "Net-(P7-A1)") (class "Default")
      (node (ref "P7") (pin "1") (pinfunction "A1_1") (pintype "passive"))
      (node (ref "U2") (pin "F1") (pinfunction "SDA_F1") (pintype "passive"))
    )
    (net (code "70") (name "Net-(P7-A2)") (class "Default")
      (node (ref "P7") (pin "4") (pinfunction "A2_4") (pintype "passive"))
      (node (ref "U2") (pin "F2") (pinfunction "SCL_F2") (pintype "passive"))
    )
    (net (code "71") (name "Net-(P7-O1)") (class "Default")
      (node (ref "P7") (pin "2") (pinfunction "O1_2") (pintype "passive"))
      (node (ref "R41") (pin "2") (pinfunction "2_2") (pintype "passive"))
    )
    (net (code "72") (name "Net-(P7-O2)") (class "Default")
      (node (ref "P7") (pin "5") (pinfunction "O2_5") (pintype "passive"))
      (node (ref "R42") (pin "2") (pinfunction "2_2") (pintype "passive"))
    )
    (net (code "73") (name "Net-(P15-Pad2)") (class "Default")
      (node (ref "P15") (pin "2") (pinfunction "2_2") (pintype "passive"))
      (node (ref "R73") (pin "2") (pinfunction "2_2") (pintype "passive"))
    )
    (net (code "74") (name "Net-(P15-Pad4)") (class "Default")
      (node (ref "P15") (pin "4") (pinfunction "4_4") (pintype "passive"))
      (node (ref "R74") (pin "2") (pinfunction "2_2") (pintype "passive"))
    )
    (net (code "75") (name "Net-(P15-Pad6)") (class "Default")
      (node (ref "P15") (pin "6") (pinfunction "6_6") (pintype "passive"))
      (node (ref "R75") (pin "2") (pinfunction "2_2") (pintype "passive"))
    )
    (net (code "76") (name "Net-(P15-Pad8)") (class "Default")
      (node (ref "P15") (pin "8") (pinfunction "8_8") (pintype "passive"))
      (node (ref "R76") (pin "2") (pinfunction "2_2") (pintype "passive"))
    )
    (net (code "77") (name "Net-(TP2-A)") (class "Default")
      (node (ref "TP2") (pin "1") (pinfunction "A_1") (pintype "passive"))
      (node (ref "U2") (pin "B4") (pinfunction "M3_VDD_IP2_OUT_B4") (pintype "passive"))
    )
    (net (code "78") (name "Net-(TP3-A)") (class "Default")
      (node (ref "TP3") (pin "1") (pinfunction "A_1") (pintype "passive"))
      (node (ref "U2") (pin "A6") (pinfunction "ANA_OUT0_A6") (pintype "passive"))
    )
    (net (code "79") (name "Net-(TP4-A)") (class "Default")
      (node (ref "TP4") (pin "1") (pinfunction "A_1") (pintype "passive"))
      (node (ref "U2") (pin "E1") (pinfunction "SDA_AOUT_E1") (pintype "passive"))
    )
    (net (code "80") (name "Net-(TP6-A)") (class "Default")
      (node (ref "TP6") (pin "1") (pinfunction "A_1") (pintype "passive"))
      (node (ref "U2") (pin "A4") (pinfunction "M3_VDD_0P6_OUT_A4") (pintype "passive"))
    )
    (net (code "81") (name "Net-(TP7-A)") (class "Default")
      (node (ref "TP7") (pin "1") (pinfunction "A_1") (pintype "passive"))
      (node (ref "U2") (pin "B6") (pinfunction "ANA_OUT1_B6") (pintype "passive"))
    )
    (net (code "82") (name "Net-(TP8-A)") (class "Default")
      (node (ref "TP8") (pin "1") (pinfunction "A_1") (pintype "passive"))
      (node (ref "U2") (pin "E2") (pinfunction "SCL_AOUT_E2") (pintype "passive"))
    )
    (net (code "83") (name "Net-(TP10-A)") (class "Default")
      (node (ref "TP10") (pin "1") (pinfunction "A_1") (pintype "passive"))
      (node (ref "U2") (pin "B7") (pinfunction "ANA_IN0_B7") (pintype "passive"))
    )
    (net (code "84") (name "Net-(TP11-A)") (class "Default")
      (node (ref "TP11") (pin "1") (pinfunction "A_1") (pintype "passive"))
      (node (ref "U2") (pin "A7") (pinfunction "ANA_IN1_A7") (pintype "passive"))
    )
    (net (code "85") (name "Net-(U1B-SCL)") (class "Default")
      (node (ref "R42") (pin "1") (pinfunction "1_1") (pintype "passive"))
      (node (ref "U1") (pin "F3") (pinfunction "SCL_F3") (pintype "passive"))
    )
    (net (code "86") (name "Net-(U1B-SDA)") (class "Default")
      (node (ref "R41") (pin "1") (pinfunction "1_1") (pintype "passive"))
      (node (ref "U1") (pin "E1") (pinfunction "SDA_E1") (pintype "passive"))
    )
    (net (code "87") (name "Net-(U1C-SPI_CLKOUT)") (class "Default")
      (node (ref "R74") (pin "1") (pinfunction "1_1") (pintype "passive"))
      (node (ref "U1") (pin "L2") (pinfunction "SPI_CLKOUT_L2") (pintype "passive"))
    )
    (net (code "88") (name "Net-(U1C-SPI_FSSOUT)") (class "Default")
      (node (ref "R75") (pin "1") (pinfunction "1_1") (pintype "passive"))
      (node (ref "U1") (pin "K3") (pinfunction "SPI_FSSOUT_K3") (pintype "passive"))
    )
    (net (code "89") (name "Net-(U1C-SPI_RXD)") (class "Default")
      (node (ref "R76") (pin "1") (pinfunction "1_1") (pintype "passive"))
      (node (ref "U1") (pin "K2") (pinfunction "SPI_RXD_K2") (pintype "passive"))
    )
    (net (code "90") (name "Net-(U1C-SPI_TXD)") (class "Default")
      (node (ref "R73") (pin "1") (pinfunction "1_1") (pintype "passive"))
      (node (ref "U1") (pin "L3") (pinfunction "SPI_TXD_L3") (pintype "passive"))
    )
    (net (code "91") (name "Net-(U1D-GPIO_0)") (class "Default")
      (node (ref "R17") (pin "1") (pinfunction "1_1") (pintype "passive"))
      (node (ref "U1") (pin "K4") (pinfunction "GPIO_0_K4") (pintype "passive"))
    )
    (net (code "92") (name "Net-(U1D-GPIO_1)") (class "Default")
      (node (ref "R18") (pin "1") (pinfunction "1_1") (pintype "passive"))
      (node (ref "U1") (pin "L4") (pinfunction "GPIO_1_L4") (pintype "passive"))
    )
    (net (code "93") (name "Net-(U1D-GPIO_2)") (class "Default")
      (node (ref "R19") (pin "1") (pinfunction "1_1") (pintype "passive"))
      (node (ref "U1") (pin "J5") (pinfunction "GPIO_2_J5") (pintype "passive"))
    )
    (net (code "94") (name "Net-(U1D-GPIO_3)") (class "Default")
      (node (ref "R20") (pin "1") (pinfunction "1_1") (pintype "passive"))
      (node (ref "U1") (pin "K5") (pinfunction "GPIO_3_K5") (pintype "passive"))
    )
    (net (code "95") (name "Net-(U1D-GPIO_4)") (class "Default")
      (node (ref "R21") (pin "1") (pinfunction "1_1") (pintype "passive"))
      (node (ref "U1") (pin "L5") (pinfunction "GPIO_4_L5") (pintype "passive"))
    )
    (net (code "96") (name "Net-(U1D-GPIO_5)") (class "Default")
      (node (ref "R22") (pin "1") (pinfunction "1_1") (pintype "passive"))
      (node (ref "U1") (pin "K6") (pinfunction "GPIO_5_K6") (pintype "passive"))
    )
    (net (code "97") (name "Net-(U1D-GPIO_6)") (class "Default")
      (node (ref "R23") (pin "1") (pinfunction "1_1") (pintype "passive"))
      (node (ref "U1") (pin "J6") (pinfunction "GPIO_6_J6") (pintype "passive"))
    )
    (net (code "98") (name "Net-(U1D-GPIO_7)") (class "Default")
      (node (ref "R24") (pin "1") (pinfunction "1_1") (pintype "passive"))
      (node (ref "U1") (pin "J7") (pinfunction "GPIO_7_J7") (pintype "passive"))
    )
    (net (code "99") (name "Net-(U1D-GPIO_8)") (class "Default")
      (node (ref "R25") (pin "1") (pinfunction "1_1") (pintype "passive"))
      (node (ref "U1") (pin "L7") (pinfunction "GPIO_8_L7") (pintype "passive"))
    )
    (net (code "100") (name "Net-(U1D-GPIO_9)") (class "Default")
      (node (ref "R26") (pin "1") (pinfunction "1_1") (pintype "passive"))
      (node (ref "U1") (pin "K7") (pinfunction "GPIO_9_K7") (pintype "passive"))
    )
    (net (code "101") (name "Net-(U1D-GPIO_10)") (class "Default")
      (node (ref "R27") (pin "1") (pinfunction "1_1") (pintype "passive"))
      (node (ref "U1") (pin "L6") (pinfunction "GPIO_10_L6") (pintype "passive"))
    )
    (net (code "102") (name "Net-(U1D-GPIO_11)") (class "Default")
      (node (ref "R28") (pin "1") (pinfunction "1_1") (pintype "passive"))
      (node (ref "U1") (pin "L8") (pinfunction "GPIO_11_L8") (pintype "passive"))
    )
    (net (code "103") (name "Net-(U1D-GPIO_12)") (class "Default")
      (node (ref "R29") (pin "1") (pinfunction "1_1") (pintype "passive"))
      (node (ref "U1") (pin "K8") (pinfunction "GPIO_12_K8") (pintype "passive"))
    )
    (net (code "104") (name "Net-(U1D-GPIO_13)") (class "Default")
      (node (ref "R30") (pin "1") (pinfunction "1_1") (pintype "passive"))
      (node (ref "U1") (pin "B10") (pinfunction "GPIO_13_B10") (pintype "passive"))
    )
    (net (code "105") (name "Net-(U1D-GPIO_14)") (class "Default")
      (node (ref "R31") (pin "1") (pinfunction "1_1") (pintype "passive"))
      (node (ref "U1") (pin "B9") (pinfunction "GPIO_14_B9") (pintype "passive"))
    )
    (net (code "106") (name "Net-(U1D-GPIO_15)") (class "Default")
      (node (ref "R32") (pin "1") (pinfunction "1_1") (pintype "passive"))
      (node (ref "U1") (pin "A10") (pinfunction "GPIO_15_A10") (pintype "passive"))
    )
    (net (code "107") (name "Net-(U1D-GPIO_16)") (class "Default")
      (node (ref "R33") (pin "1") (pinfunction "1_1") (pintype "passive"))
      (node (ref "U1") (pin "A9") (pinfunction "GPIO_16_A9") (pintype "passive"))
    )
    (net (code "108") (name "Net-(U1D-GPIO_17)") (class "Default")
      (node (ref "R34") (pin "1") (pinfunction "1_1") (pintype "passive"))
      (node (ref "U1") (pin "B8") (pinfunction "GPIO_17_B8") (pintype "passive"))
    )
    (net (code "109") (name "Net-(U1D-GPIO_18)") (class "Default")
      (node (ref "R35") (pin "1") (pinfunction "1_1") (pintype "passive"))
      (node (ref "U1") (pin "A8") (pinfunction "GPIO_18_A8") (pintype "passive"))
    )
    (net (code "110") (name "Net-(U1D-GPIO_19)") (class "Default")
      (node (ref "R36") (pin "1") (pinfunction "1_1") (pintype "passive"))
      (node (ref "U1") (pin "B6") (pinfunction "GPIO_19_B6") (pintype "passive"))
    )
    (net (code "111") (name "Net-(U1D-GPIO_20)") (class "Default")
      (node (ref "R37") (pin "1") (pinfunction "1_1") (pintype "passive"))
      (node (ref "U1") (pin "B7") (pinfunction "GPIO_20_B7") (pintype "passive"))
    )
    (net (code "112") (name "Net-(U1D-GPIO_21)") (class "Default")
      (node (ref "R38") (pin "1") (pinfunction "1_1") (pintype "passive"))
      (node (ref "U1") (pin "A7") (pinfunction "GPIO_21_A7") (pintype "passive"))
    )
    (net (code "113") (name "Net-(U1D-GPIO_22)") (class "Default")
      (node (ref "R39") (pin "1") (pinfunction "1_1") (pintype "passive"))
      (node (ref "U1") (pin "C7") (pinfunction "GPIO_22_C7") (pintype "passive"))
    )
    (net (code "114") (name "Net-(U1D-GPIO_23)") (class "Default")
      (node (ref "R40") (pin "1") (pinfunction "1_1") (pintype "passive"))
      (node (ref "U1") (pin "C6") (pinfunction "GPIO_23_C6") (pintype "passive"))
    )
    (net (code "115") (name "Net-(U2A-PC_CLK)") (class "Default")
      (node (ref "R81") (pin "2") (pinfunction "2_2") (pintype "passive"))
      (node (ref "U2") (pin "F9") (pinfunction "PC_CLK_F9") (pintype "passive"))
    )
    (net (code "116") (name "Net-(U2A-PC_RDDATA_OUT)") (class "Default")
      (node (ref "R83") (pin "2") (pinfunction "2_2") (pintype "passive"))
      (node (ref "U2") (pin "G10") (pinfunction "PC_RDDATA_OUT_G10") (pintype "passive"))
    )
    (net (code "117") (name "Net-(U2A-PC_RDRDY_OUT)") (class "Default")
      (node (ref "R82") (pin "2") (pinfunction "2_2") (pintype "passive"))
      (node (ref "U2") (pin "F10") (pinfunction "PC_RDRDY_OUT_F10") (pintype "passive"))
    )
    (net (code "118") (name "Net-(U2A-PC_RDREQ)") (class "Default")
      (node (ref "R84") (pin "2") (pinfunction "2_2") (pintype "passive"))
      (node (ref "U2") (pin "J7") (pinfunction "PC_RDREQ_J7") (pintype "passive"))
    )
    (net (code "119") (name "Net-(U2A-PC_RESETN)") (class "Default")
      (node (ref "R85") (pin "2") (pinfunction "2_2") (pintype "passive"))
      (node (ref "U2") (pin "K7") (pinfunction "PC_RESETN_K7") (pintype "passive"))
    )
    (net (code "120") (name "Net-(U2A-PC_WRDATA)") (class "Default")
      (node (ref "R80") (pin "2") (pinfunction "2_2") (pintype "passive"))
      (node (ref "U2") (pin "E10") (pinfunction "PC_WRDATA_E10") (pintype "passive"))
    )
    (net (code "121") (name "Net-(U2A-PC_WRREQ)") (class "Default")
      (node (ref "R79") (pin "2") (pinfunction "2_2") (pintype "passive"))
      (node (ref "U2") (pin "E9") (pinfunction "PC_WRREQ_E9") (pintype "passive"))
    )
    (net (code "122") (name "Net-(U2C-VDD_ABUF)") (class "Default")
      (node (ref "C59") (pin "2") (pinfunction "2_2") (pintype "passive"))
      (node (ref "P5") (pin "3") (pinfunction "3_3") (pintype "passive"))
      (node (ref "U2") (pin "D9") (pinfunction "VDD_ABUF_D9") (pintype "passive"))
    )
    (net (code "123") (name "Net-(U2D-M3_VDD_0P6)") (class "Default")
      (node (ref "P4") (pin "3") (pinfunction "3_3") (pintype "passive"))
      (node (ref "U2") (pin "D2") (pinfunction "M3_VDD_0P6_D2") (pintype "passive"))
    )
    (net (code "124") (name "Net-(U2D-M3_VDD_1P2)") (class "Default")
      (node (ref "P4") (pin "1") (pinfunction "1_1") (pintype "passive"))
      (node (ref "U2") (pin "D1") (pinfunction "M3_VDD_1P2_D1") (pintype "passive"))
    )
    (net (code "125") (name "SCL_DIG") (class "Default")
      (node (ref "TP5") (pin "1") (pinfunction "A_1") (pintype "passive"))
      (node (ref "U2") (pin "K4") (pinfunction "SCL_DOUT_K4") (pintype "passive"))
    )
    (net (code "126") (name "SDA_DIG") (class "Default")
      (node (ref "TP9") (pin "1") (pinfunction "A_1") (pintype "passive"))
      (node (ref "U2") (pin "K5") (pinfunction "SDA_DOUT_K5") (pintype "passive"))
    )
    (net (code "127") (name "VCC_M3_0P6") (class "Default")
      (node (ref "P2") (pin "3") (pinfunction "3_3") (pintype "passive"))
    )
    (net (code "128") (name "VCC_M3_1P2") (class "Default")
      (node (ref "P2") (pin "5") (pinfunction "5_5") (pintype "passive"))
      (node (ref "P5") (pin "6") (pinfunction "6_6") (pintype "passive"))
    )
    (net (code "129") (name "VCC_M3_VBATT") (class "Default")
      (node (ref "P2") (pin "7") (pinfunction "7_7") (pintype "passive"))
      (node (ref "P5") (pin "2") (pinfunction "2_2") (pintype "passive"))
      (node (ref "P5") (pin "4") (pinfunction "4_4") (pintype "passive"))
    )
    (net (code "130") (name "VCC_SOL") (class "Default")
      (node (ref "P2") (pin "1") (pinfunction "1_1") (pintype "passive"))
    )
  )
)
